# Tui.net
KiCad netlist of a schematic drawn in Altium Designer
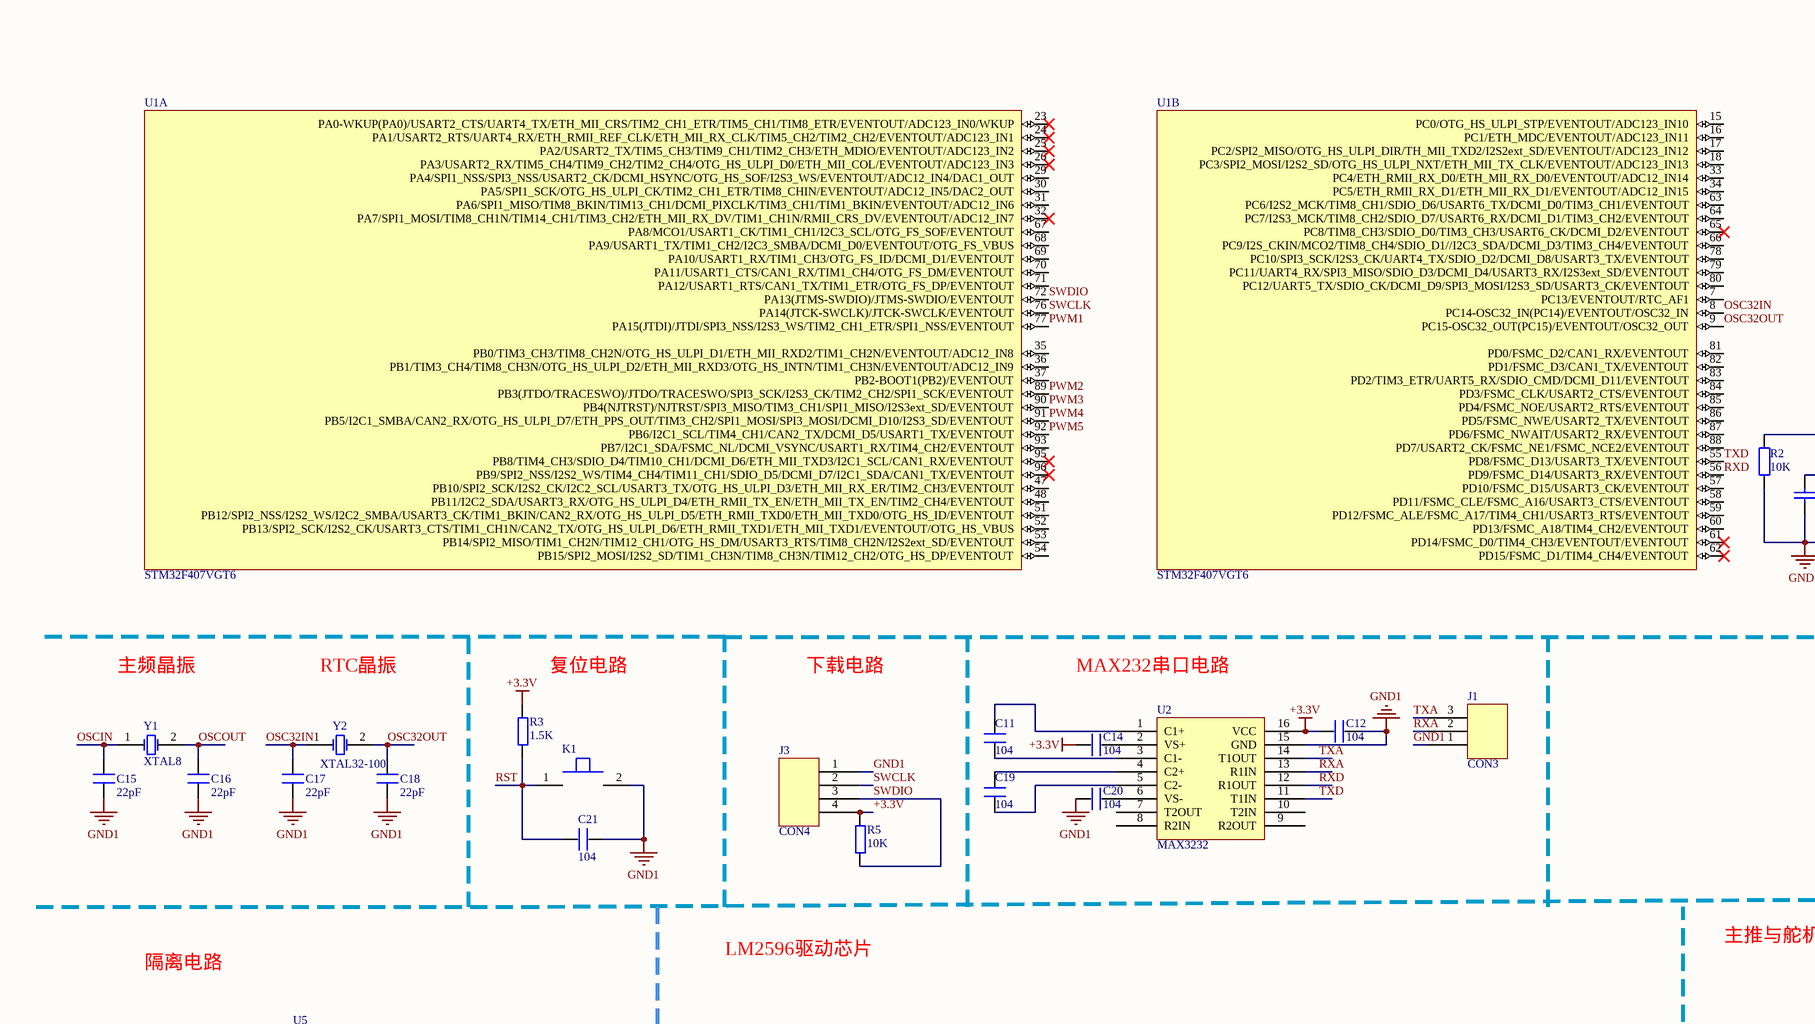
[diagram p0: Tui.SchDoc, top left]
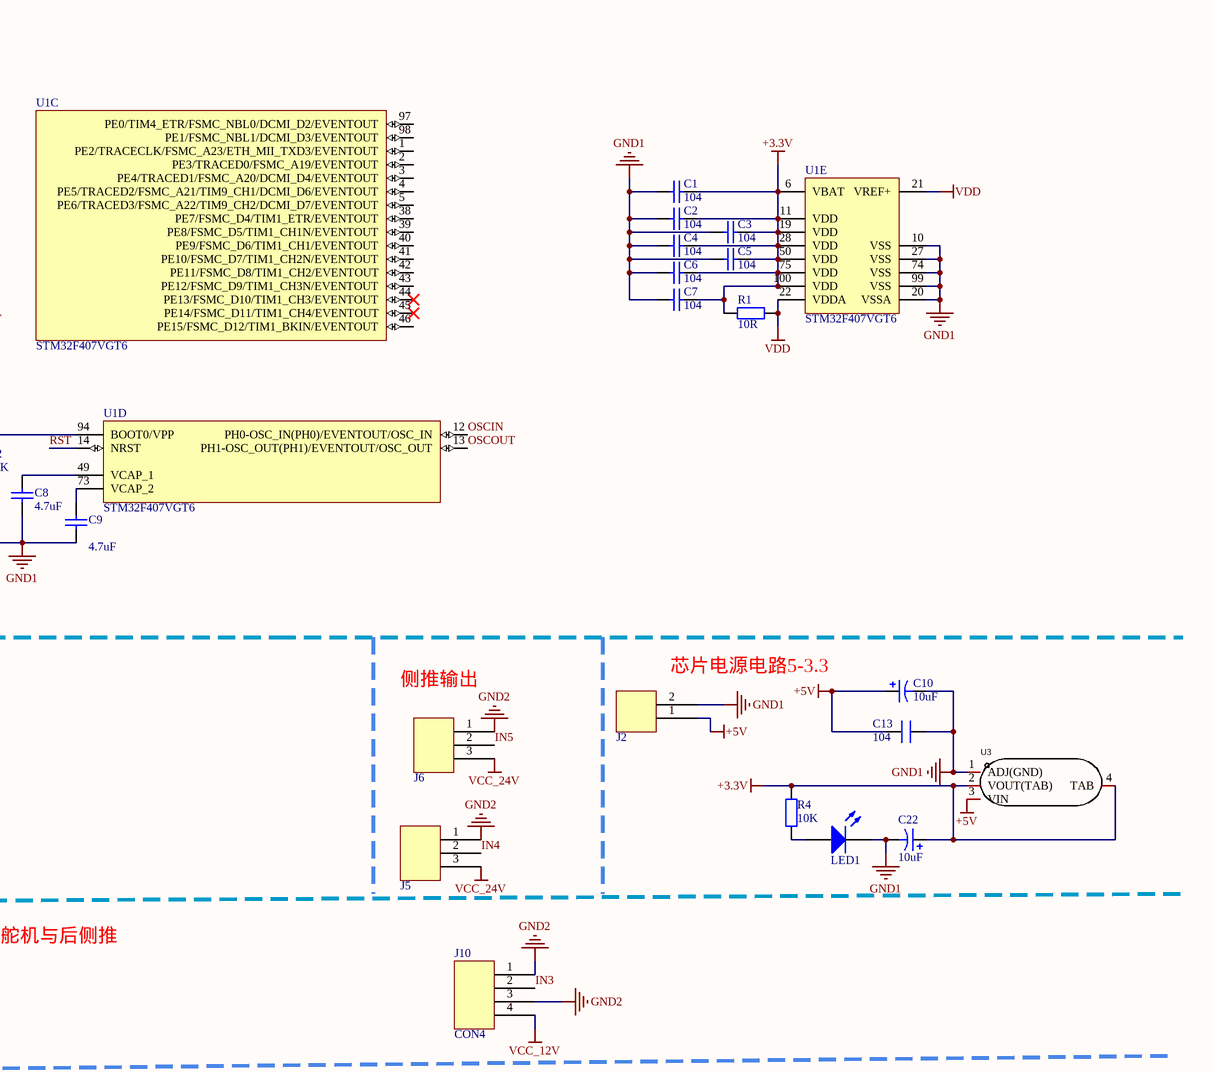
[diagram p1: Tui.SchDoc, top right]
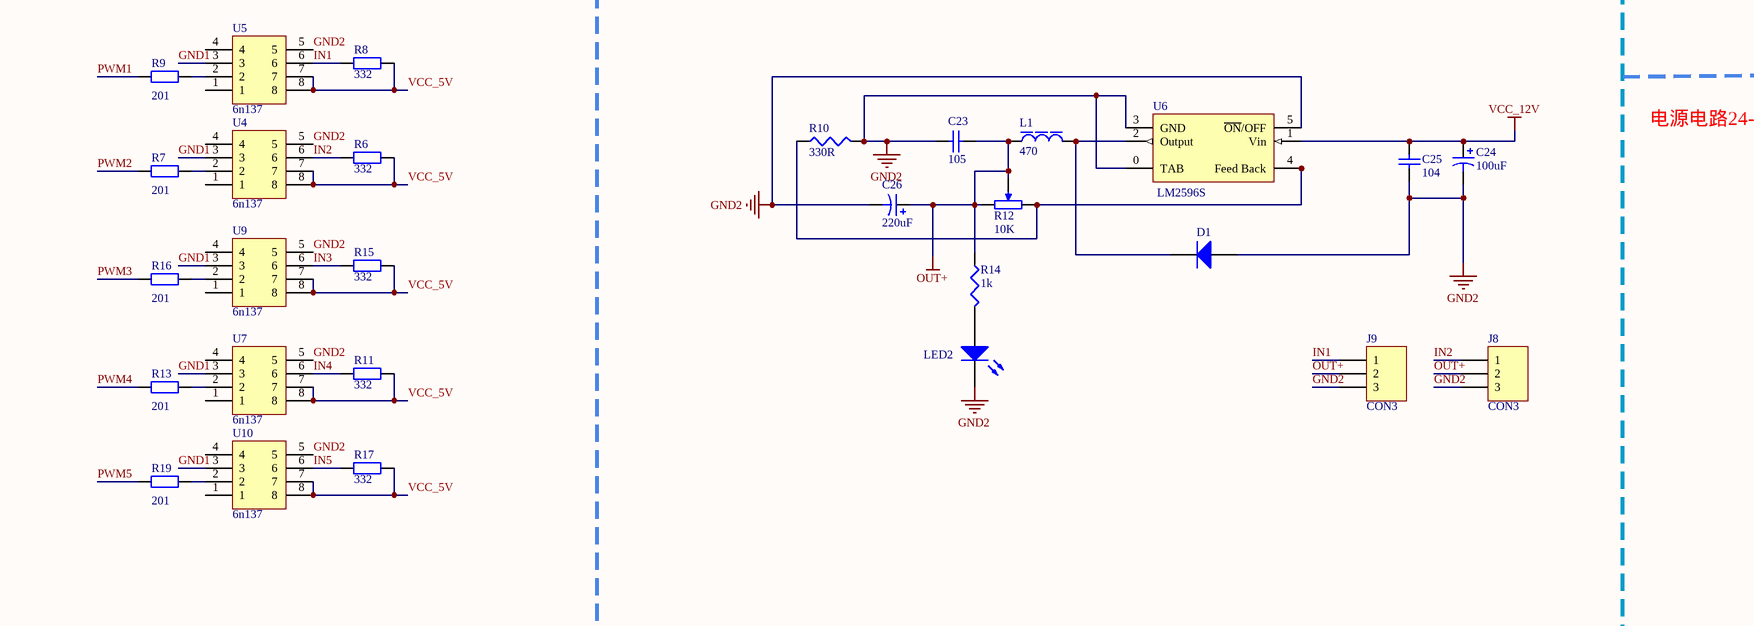
[diagram p2: Tui.SchDoc, bottom left]
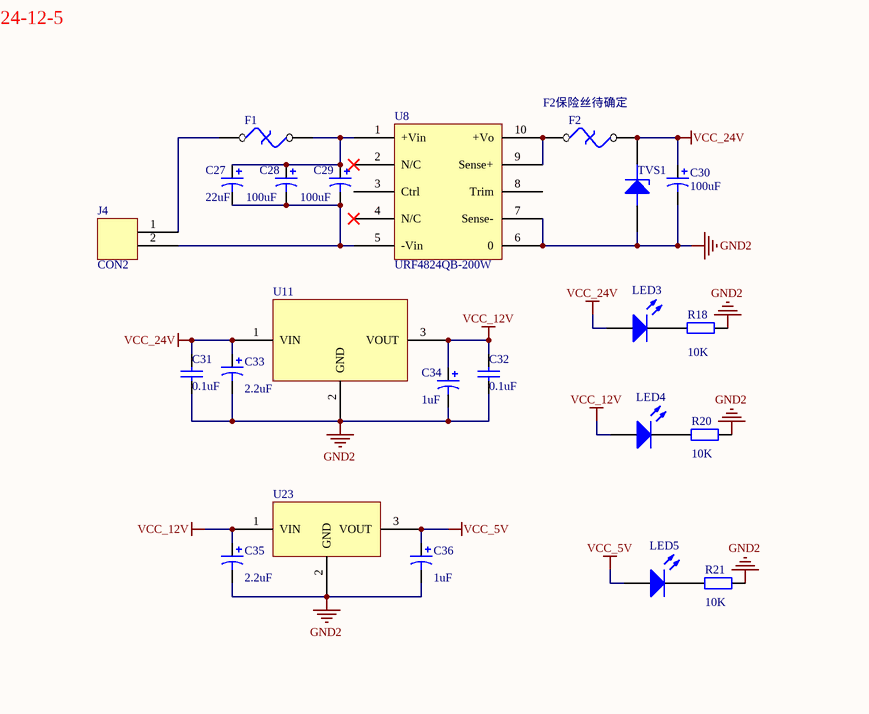
[diagram p3: Tui.SchDoc, bottom right]

(export (version "E")
  (design (tool "Eeschema 10.0.6"))
  (components
    (comp (ref "C1")
      (value "104")
      (footprint "0805")
      (description "Capacitor")
      (fields (field (name "PUBLISHER") "Altium Limited"))
      (libsource (lib "Miscellaneous Devices") (part "Cap"))
    )
    (comp (ref "C2")
      (value "104")
      (footprint "0805")
      (description "Capacitor")
      (fields (field (name "PUBLISHER") "Altium Limited"))
      (libsource (lib "Miscellaneous Devices") (part "Cap"))
    )
    (comp (ref "C3")
      (value "104")
      (footprint "0805")
      (description "Capacitor")
      (fields (field (name "PUBLISHER") "Altium Limited"))
      (libsource (lib "Miscellaneous Devices") (part "Cap"))
    )
    (comp (ref "C4")
      (value "104")
      (footprint "0805")
      (description "Capacitor")
      (fields (field (name "PUBLISHER") "Altium Limited"))
      (libsource (lib "Miscellaneous Devices") (part "Cap"))
    )
    (comp (ref "C5")
      (value "104")
      (footprint "0805")
      (description "Capacitor")
      (fields (field (name "PUBLISHER") "Altium Limited"))
      (libsource (lib "Miscellaneous Devices") (part "Cap"))
    )
    (comp (ref "C6")
      (value "104")
      (footprint "0805")
      (description "Capacitor")
      (fields (field (name "PUBLISHER") "Altium Limited"))
      (libsource (lib "Miscellaneous Devices") (part "Cap"))
    )
    (comp (ref "C7")
      (value "104")
      (footprint "0805")
      (description "Capacitor")
      (fields (field (name "PUBLISHER") "Altium Limited"))
      (libsource (lib "Miscellaneous Devices") (part "Cap"))
    )
    (comp (ref "C8")
      (value "4.7uF")
      (footprint "0805")
      (description "Capacitor")
      (fields (field (name "PUBLISHER") "Altium Limited"))
      (libsource (lib "Miscellaneous Devices") (part "Cap"))
    )
    (comp (ref "C9")
      (value "4.7uF")
      (footprint "0805")
      (description "Capacitor")
      (fields (field (name "PUBLISHER") "Altium Limited"))
      (libsource (lib "Miscellaneous Devices") (part "Cap"))
    )
    (comp (ref "C10")
      (value "10uF")
      (footprint "钽电容小")
      (description "Polarized Capacitor (Radial)")
      (fields (field (name "Comment") "Cap Pol1") (field (name "PUBLISHER") "Altium Limited"))
      (libsource (lib "Miscellaneous Devices") (part "Cap Pol1"))
    )
    (comp (ref "C11") (value "104") (footprint "0805") (libsource (lib "stm32") (part "CAP")))
    (comp (ref "C12") (value "104") (footprint "0805") (libsource (lib "stm32") (part "CAP")))
    (comp (ref "C13") (value "104") (footprint "0805") (libsource (lib "stm32") (part "CAP")))
    (comp (ref "C14") (value "104") (footprint "0805") (libsource (lib "stm32") (part "CAP")))
    (comp (ref "C15") (value "22pF") (footprint "0805") (libsource (lib "stm32") (part "CAP")))
    (comp (ref "C16") (value "22pF") (footprint "0805") (libsource (lib "stm32") (part "CAP")))
    (comp (ref "C17") (value "22pF") (footprint "0805") (libsource (lib "stm32") (part "CAP")))
    (comp (ref "C18") (value "22pF") (footprint "0805") (libsource (lib "stm32") (part "CAP")))
    (comp (ref "C19") (value "104") (footprint "0805") (libsource (lib "stm32") (part "CAP")))
    (comp (ref "C20") (value "104") (footprint "0805") (libsource (lib "stm32") (part "CAP")))
    (comp (ref "C21") (value "104") (footprint "0805") (libsource (lib "stm32") (part "CAP")))
    (comp (ref "C22")
      (value "10uF")
      (footprint "钽电容小")
      (description "Polarized Capacitor (Radial)")
      (fields (field (name "Comment") "Cap Pol1") (field (name "PUBLISHER") "Altium Limited"))
      (libsource (lib "Miscellaneous Devices") (part "Cap Pol1"))
    )
    (comp (ref "C23")
      (value "105")
      (footprint "0805")
      (description "Capacitor (Semiconductor SIM Model)")
      (libsource (lib "FPGA_A") (part "Cap Semi"))
    )
    (comp (ref "C24")
      (value "100uF")
      (footprint "CAP+")
      (description "Polarized Capacitor (Radial)")
      (fields (field (name "Comment") "107T") (field (name "PUBLISHER") "Altium Limited"))
      (libsource (lib "FPGA_A") (part "Cap Pol1"))
    )
    (comp (ref "C25")
      (value "104")
      (footprint "0805")
      (description "Capacitor (Semiconductor SIM Model)")
      (libsource (lib "FPGA_A") (part "Cap Semi_1"))
    )
    (comp (ref "C26")
      (value "220uF")
      (footprint "CAP+")
      (description "Polarized Capacitor (Radial)")
      (fields (field (name "Comment") "227V") (field (name "PUBLISHER") "Altium Limited"))
      (libsource (lib "FPGA_A") (part "Cap Pol1"))
    )
    (comp (ref "C27")
      (value "22uF")
      (footprint "钽电容大")
      (description "Polarized Capacitor (Radial)")
      (fields (field (name "Comment") "Cap Pol1") (field (name "PUBLISHER") "Altium Limited"))
      (libsource (lib "Miscellaneous Devices") (part "Cap Pol1"))
    )
    (comp (ref "C28")
      (value "100uF")
      (footprint "钽电容大")
      (description "Polarized Capacitor (Radial)")
      (fields (field (name "Comment") "Cap Pol1") (field (name "PUBLISHER") "Altium Limited"))
      (libsource (lib "Miscellaneous Devices") (part "Cap Pol1"))
    )
    (comp (ref "C29")
      (value "100uF")
      (footprint "钽电容大")
      (description "Polarized Capacitor (Radial)")
      (fields (field (name "Comment") "Cap Pol1") (field (name "PUBLISHER") "Altium Limited"))
      (libsource (lib "Miscellaneous Devices") (part "Cap Pol1"))
    )
    (comp (ref "C30")
      (value "100uF")
      (footprint "钽电容大")
      (description "Polarized Capacitor (Radial)")
      (fields (field (name "Comment") "Cap Pol1") (field (name "PUBLISHER") "Altium Limited"))
      (libsource (lib "Miscellaneous Devices") (part "Cap Pol1"))
    )
    (comp (ref "C31")
      (value "0.1uF")
      (footprint "0805")
      (description "Capacitor")
      (fields (field (name "PUBLISHER") "Altium Limited"))
      (libsource (lib "Miscellaneous Devices") (part "Cap"))
    )
    (comp (ref "C32")
      (value "0.1uF")
      (footprint "0805")
      (description "Capacitor")
      (fields (field (name "PUBLISHER") "Altium Limited"))
      (libsource (lib "Miscellaneous Devices") (part "Cap"))
    )
    (comp (ref "C33")
      (value "2.2uF")
      (footprint "钽电容小")
      (description "Polarized Capacitor (Radial)")
      (fields (field (name "Comment") "Cap Pol1") (field (name "PUBLISHER") "Altium Limited"))
      (libsource (lib "Miscellaneous Devices") (part "Cap Pol1"))
    )
    (comp (ref "C34")
      (value "1uF")
      (footprint "钽电容小")
      (description "Polarized Capacitor (Radial)")
      (fields (field (name "Comment") "Cap Pol1") (field (name "PUBLISHER") "Altium Limited"))
      (libsource (lib "Miscellaneous Devices") (part "Cap Pol1"))
    )
    (comp (ref "C35")
      (value "2.2uF")
      (footprint "钽电容小")
      (description "Polarized Capacitor (Radial)")
      (fields (field (name "Comment") "Cap Pol1") (field (name "PUBLISHER") "Altium Limited"))
      (libsource (lib "Miscellaneous Devices") (part "Cap Pol1"))
    )
    (comp (ref "C36")
      (value "1uF")
      (footprint "钽电容小")
      (description "Polarized Capacitor (Radial)")
      (fields (field (name "Comment") "Cap Pol1") (field (name "PUBLISHER") "Altium Limited"))
      (libsource (lib "Miscellaneous Devices") (part "Cap Pol1"))
    )
    (comp (ref "D1") (value "DIODE") (footprint "SS34") (libsource (lib "原理图库") (part "DIODE")))
    (comp (ref "F1")
      (value "THERMAL FUSE")
      (footprint "1206")
      (libsource (lib "Miscellaneous Devices") (part "THERMAL FUSE"))
    )
    (comp (ref "F2")
      (value "THERMAL FUSE")
      (footprint "1206")
      (libsource (lib "Miscellaneous Devices") (part "THERMAL FUSE"))
    )
    (comp (ref "J1") (value "CON3") (footprint "CON3BB") (libsource (lib "") (part "CON3_1")))
    (comp (ref "J2")
      (value "CON2")
      (footprint "CONN-TH_2P-P3.81_DB2EVC-3.81-2P-BK")
      (libsource (lib "stm32") (part "CON2"))
    )
    (comp (ref "J3") (value "CON4") (footprint "CON4") (libsource (lib "stm32") (part "CON4")))
    (comp (ref "J4")
      (value "CON2")
      (footprint "CONN-TH_2P-P3.81_DB2EVC-3.81-2P-BK")
      (libsource (lib "") (part "CON2_1"))
    )
    (comp (ref "J5")
      (value "CON3")
      (footprint "CONN-TH_3P-P3.81_DB2EVC-3.81-3P")
      (libsource (lib "stm32") (part "CON3"))
    )
    (comp (ref "J6")
      (value "CON3")
      (footprint "CONN-TH_3P-P3.81_DB2EVC-3.81-3P")
      (libsource (lib "stm32") (part "CON3"))
    )
    (comp (ref "J8")
      (value "CON3")
      (footprint "CONN-TH_3P-P3.81_DB2EVC-3.81-3P")
      (description "Header, 3-Pin")
      (fields (field (name "PUBLISHER") "Altium Limited"))
      (libsource (lib "Miscellaneous Connectors") (part "Header 3"))
    )
    (comp (ref "J9")
      (value "CON3")
      (footprint "CONN-TH_3P-P3.81_DB2EVC-3.81-3P")
      (description "Header, 3-Pin")
      (fields (field (name "PUBLISHER") "Altium Limited"))
      (libsource (lib "Miscellaneous Connectors") (part "Header 3"))
    )
    (comp (ref "J10")
      (value "CON4")
      (footprint "CONN-TH_4P-P3.81_DB2EVC-3.81-4P")
      (libsource (lib "stm32") (part "CON4"))
    )
    (comp (ref "K1") (value "KEY4") (footprint "按钮") (libsource (lib "stm32") (part "KEY4")))
    (comp (ref "L1") (value "470") (footprint "470") (libsource (lib "原理图库") (part "470")))
    (comp (ref "LED1")
      (value "LED")
      (footprint "0805")
      (fields (field (name "PUBLISHER") "Altium Limited"))
      (libsource (lib "stm32") (part "LED"))
    )
    (comp (ref "LED2")
      (value "~")
      (footprint "0805")
      (description "Typical RED, GREEN, YELLOW, AMBER GaAs LED")
      (libsource (lib "Miscellaneous Devices") (part "LED2"))
    )
    (comp (ref "LED3")
      (value "LED")
      (footprint "0805")
      (fields (field (name "PUBLISHER") "Altium Limited"))
      (libsource (lib "stm32") (part "LED"))
    )
    (comp (ref "LED4")
      (value "LED")
      (footprint "0805")
      (fields (field (name "PUBLISHER") "Altium Limited"))
      (libsource (lib "stm32") (part "LED"))
    )
    (comp (ref "LED5")
      (value "LED")
      (footprint "0805")
      (fields (field (name "PUBLISHER") "Altium Limited"))
      (libsource (lib "stm32") (part "LED"))
    )
    (comp (ref "R1")
      (value "10R")
      (footprint "0805")
      (description "Resistor")
      (fields (field (name "PUBLISHER") "Altium Limited"))
      (libsource (lib "") (part "Res2_1"))
    )
    (comp (ref "R2")
      (value "10K")
      (footprint "0805")
      (description "Resistor")
      (fields (field (name "PUBLISHER") "Altium Limited"))
      (libsource (lib "") (part "Res2_3"))
    )
    (comp (ref "R3") (value "1.5K") (footprint "0805") (libsource (lib "stm32") (part "RES")))
    (comp (ref "R4")
      (value "10K")
      (footprint "0805")
      (description "Resistor")
      (fields (field (name "PUBLISHER") "Altium Limited"))
      (libsource (lib "") (part "Res2_2"))
    )
    (comp (ref "R5") (value "10K") (footprint "0805") (libsource (lib "stm32") (part "RES")))
    (comp (ref "R6")
      (value "332")
      (footprint "0805")
      (description "Resistor")
      (fields (field (name "PUBLISHER") "Altium Limited"))
      (libsource (lib "") (part "Res2_1"))
    )
    (comp (ref "R7")
      (value "201")
      (footprint "0805")
      (description "Resistor")
      (fields (field (name "PUBLISHER") "Altium Limited"))
      (libsource (lib "Miscellaneous Devices") (part "Res2"))
    )
    (comp (ref "R8")
      (value "332")
      (footprint "0805")
      (description "Resistor")
      (fields (field (name "PUBLISHER") "Altium Limited"))
      (libsource (lib "") (part "Res2_1"))
    )
    (comp (ref "R9")
      (value "201")
      (footprint "0805")
      (description "Resistor")
      (fields (field (name "PUBLISHER") "Altium Limited"))
      (libsource (lib "Miscellaneous Devices") (part "Res2"))
    )
    (comp (ref "R10")
      (value "330R")
      (footprint "0805")
      (description "Resistor")
      (libsource (lib "FPGA_A") (part "Res3"))
    )
    (comp (ref "R11")
      (value "332")
      (footprint "0805")
      (description "Resistor")
      (fields (field (name "PUBLISHER") "Altium Limited"))
      (libsource (lib "") (part "Res2_1"))
    )
    (comp (ref "R12") (value "10K") (footprint "RESPACK") (libsource (lib "原理图库") (part "RESPACK")))
    (comp (ref "R13")
      (value "201")
      (footprint "0805")
      (description "Resistor")
      (fields (field (name "PUBLISHER") "Altium Limited"))
      (libsource (lib "Miscellaneous Devices") (part "Res2"))
    )
    (comp (ref "R14") (value "1k") (footprint "0805") (libsource (lib "FPGA_A") (part "RES")))
    (comp (ref "R15")
      (value "332")
      (footprint "0805")
      (description "Resistor")
      (fields (field (name "PUBLISHER") "Altium Limited"))
      (libsource (lib "") (part "Res2_1"))
    )
    (comp (ref "R16")
      (value "201")
      (footprint "0805")
      (description "Resistor")
      (fields (field (name "PUBLISHER") "Altium Limited"))
      (libsource (lib "Miscellaneous Devices") (part "Res2"))
    )
    (comp (ref "R17")
      (value "332")
      (footprint "0805")
      (description "Resistor")
      (fields (field (name "PUBLISHER") "Altium Limited"))
      (libsource (lib "") (part "Res2_1"))
    )
    (comp (ref "R18")
      (value "10K")
      (footprint "0805")
      (description "Resistor")
      (fields (field (name "Comment") "Res2") (field (name "PUBLISHER") "Altium Limited"))
      (libsource (lib "Miscellaneous Devices") (part "Res2"))
    )
    (comp (ref "R19")
      (value "201")
      (footprint "0805")
      (description "Resistor")
      (fields (field (name "PUBLISHER") "Altium Limited"))
      (libsource (lib "Miscellaneous Devices") (part "Res2"))
    )
    (comp (ref "R20")
      (value "10K")
      (footprint "0805")
      (description "Resistor")
      (fields (field (name "PUBLISHER") "Altium Limited"))
      (libsource (lib "Miscellaneous Devices") (part "Res2"))
    )
    (comp (ref "R21")
      (value "10K")
      (footprint "0805")
      (description "Resistor")
      (fields (field (name "PUBLISHER") "Altium Limited"))
      (libsource (lib "Miscellaneous Devices") (part "Res2"))
    )
    (comp (ref "TVS1")
      (value "TVS")
      (footprint "tvs")
      (description "Zener Diode")
      (libsource (lib "二极管") (part "稳压二极管"))
    )
    (comp (ref "U1")
      (value "STM32F407VGT6")
      (footprint "STM32F407VGT6")
      (libsource (lib "STM32 F4") (part "STM32F407VGT6"))
    )
    (comp (ref "U2") (value "MAX3232") (footprint "max3232") (libsource (lib "Schlib1") (part "MAX3232")))
    (comp (ref "U3")
      (value "AMS1117-3.3_C347222")
      (footprint "AMS1117")
      (fields (field (name "MANUFACTURER") "UMW(广东友台半导体)") (field (name "MANUFACTURER PART") "AMS1117-3.3"))
      (libsource (lib "altium-import") (part "root_0_AMS1117-3.3_C347222_"))
    )
    (comp (ref "U4") (value "6n137") (footprint "6n137") (libsource (lib "6n137") (part "6n137")))
    (comp (ref "U5") (value "6n137") (footprint "6n137") (libsource (lib "6n137") (part "6n137")))
    (comp (ref "U6") (value "LM2596S") (footprint "LM2596S") (libsource (lib "原理图库") (part "LM2596S")))
    (comp (ref "U7") (value "6n137") (footprint "6n137") (libsource (lib "6n137") (part "6n137")))
    (comp (ref "U8")
      (value "URF4824QB-200W")
      (footprint "URF4824QB-200W（24稳压）")
      (libsource (lib "Schlib1") (part "URF4824QB-200W"))
    )
    (comp (ref "U9") (value "6n137") (footprint "6n137") (libsource (lib "6n137") (part "6n137")))
    (comp (ref "U10") (value "6n137") (footprint "6n137") (libsource (lib "6n137") (part "6n137")))
    (comp (ref "U11") (value "7812") (footprint "7812") (libsource (lib "Schlib1") (part "L7912CV")))
    (comp (ref "U23") (value "7805") (footprint "7805") (libsource (lib "Schlib1") (part "7805")))
    (comp (ref "Y1")
      (value "XTAL8")
      (footprint "XTAL8（晶振）")
      (fields (field (name "PUBLISHER") "Altium Limited"))
      (libsource (lib "stm32") (part "XTAL8"))
    )
    (comp (ref "Y2")
      (value "XTAL32-100")
      (footprint "XTAL32-100（晶振）")
      (fields (field (name "PUBLISHER") "Altium Limited"))
      (libsource (lib "stm32") (part "XTAL32-100"))
    )
  )
  (nets
    (net (code "1") (name "+3.3V") (class "Default")
      (node (ref "C1") (pin "1") (pinfunction "1_1") (pintype "passive"))
      (node (ref "C12") (pin "1") (pintype "passive"))
      (node (ref "C14") (pin "2") (pintype "passive"))
      (node (ref "C2") (pin "1") (pinfunction "1_1") (pintype "passive"))
      (node (ref "C22") (pin "1") (pinfunction "1_1") (pintype "passive"))
      (node (ref "C3") (pin "1") (pinfunction "1_1") (pintype "passive"))
      (node (ref "C4") (pin "1") (pinfunction "1_1") (pintype "passive"))
      (node (ref "C5") (pin "1") (pinfunction "1_1") (pintype "passive"))
      (node (ref "C6") (pin "1") (pinfunction "1_1") (pintype "passive"))
      (node (ref "C7") (pin "1") (pinfunction "1_1") (pintype "passive"))
      (node (ref "J3") (pin "4") (pinfunction "4_4") (pintype "passive"))
      (node (ref "R1") (pin "2") (pinfunction "2_2") (pintype "passive"))
      (node (ref "R3") (pin "2") (pintype "passive"))
      (node (ref "R4") (pin "2") (pinfunction "2_2") (pintype "passive"))
      (node (ref "R5") (pin "2") (pintype "passive"))
      (node (ref "U1") (pin "100") (pinfunction "VDD_100") (pintype "power_in"))
      (node (ref "U1") (pin "11") (pinfunction "VDD_11") (pintype "power_in"))
      (node (ref "U1") (pin "19") (pinfunction "VDD_19") (pintype "power_in"))
      (node (ref "U1") (pin "28") (pinfunction "VDD_28") (pintype "power_in"))
      (node (ref "U1") (pin "50") (pinfunction "VDD_50") (pintype "power_in"))
      (node (ref "U1") (pin "6") (pinfunction "VBAT_6") (pintype "power_in"))
      (node (ref "U1") (pin "75") (pinfunction "VDD_75") (pintype "power_in"))
      (node (ref "U2") (pin "16") (pinfunction "VCC_16") (pintype "power_in"))
      (node (ref "U3") (pin "2") (pinfunction "VOUT(TAB)_2") (pintype "passive"))
      (node (ref "U3") (pin "4") (pinfunction "TAB_4") (pintype "passive"))
    )
    (net (code "2") (name "+5V") (class "Default")
      (node (ref "C10") (pin "1") (pinfunction "1_1") (pintype "passive"))
      (node (ref "C13") (pin "2") (pintype "passive"))
      (node (ref "J2") (pin "1") (pinfunction "1_1") (pintype "passive"))
      (node (ref "U3") (pin "3") (pinfunction "VIN_3") (pintype "passive"))
    )
    (net (code "3") (name "/IN1") (class "Default")
      (node (ref "J9") (pin "1") (pinfunction "1_1") (pintype "passive"))
      (node (ref "R8") (pin "2") (pinfunction "2_2") (pintype "passive"))
      (node (ref "U5") (pin "6") (pinfunction "6_6") (pintype "passive"))
    )
    (net (code "4") (name "/IN2") (class "Default")
      (node (ref "J8") (pin "1") (pinfunction "1_1") (pintype "passive"))
      (node (ref "R6") (pin "2") (pinfunction "2_2") (pintype "passive"))
      (node (ref "U4") (pin "6") (pinfunction "6_6") (pintype "passive"))
    )
    (net (code "5") (name "/IN3") (class "Default")
      (node (ref "J10") (pin "2") (pinfunction "2_2") (pintype "passive"))
      (node (ref "R15") (pin "2") (pinfunction "2_2") (pintype "passive"))
      (node (ref "U9") (pin "6") (pinfunction "6_6") (pintype "passive"))
    )
    (net (code "6") (name "/IN4") (class "Default")
      (node (ref "J5") (pin "2") (pinfunction "2_2") (pintype "passive"))
      (node (ref "R11") (pin "2") (pinfunction "2_2") (pintype "passive"))
      (node (ref "U7") (pin "6") (pinfunction "6_6") (pintype "passive"))
    )
    (net (code "7") (name "/IN5") (class "Default")
      (node (ref "J6") (pin "2") (pinfunction "2_2") (pintype "passive"))
      (node (ref "R17") (pin "2") (pinfunction "2_2") (pintype "passive"))
      (node (ref "U10") (pin "6") (pinfunction "6_6") (pintype "passive"))
    )
    (net (code "8") (name "/OSC32IN") (class "Default")
      (node (ref "C17") (pin "2") (pintype "passive"))
      (node (ref "U1") (pin "8") (pinfunction "PC14-OSC32_IN(PC14)/EVENTOUT/OSC32_IN_8") (pintype "bidirectional"))
      (node (ref "Y2") (pin "1") (pinfunction "OSC1_1") (pintype "passive"))
    )
    (net (code "9") (name "/OSC32OUT") (class "Default")
      (node (ref "C18") (pin "2") (pintype "passive"))
      (node (ref "U1") (pin "9") (pinfunction "PC15-OSC32_OUT(PC15)/EVENTOUT/OSC32_OUT_9") (pintype "bidirectional"))
      (node (ref "Y2") (pin "2") (pinfunction "OSC2_2") (pintype "passive"))
    )
    (net (code "10") (name "/OSCIN") (class "Default")
      (node (ref "C15") (pin "2") (pintype "passive"))
      (node (ref "U1") (pin "12") (pinfunction "PH0-OSC_IN(PH0)/EVENTOUT/OSC_IN_12") (pintype "bidirectional"))
      (node (ref "Y1") (pin "1") (pinfunction "OSC1_1") (pintype "passive"))
    )
    (net (code "11") (name "/OSCOUT") (class "Default")
      (node (ref "C16") (pin "2") (pintype "passive"))
      (node (ref "U1") (pin "13") (pinfunction "PH1-OSC_OUT(PH1)/EVENTOUT/OSC_OUT_13") (pintype "bidirectional"))
      (node (ref "Y1") (pin "2") (pinfunction "OSC2_2") (pintype "passive"))
    )
    (net (code "12") (name "/PWM1") (class "Default")
      (node (ref "R9") (pin "1") (pinfunction "1_1") (pintype "passive"))
      (node (ref "U1") (pin "77") (pinfunction "PA15(JTDI)/JTDI/SPI3_NSS/I2S3_WS/TIM2_CH1_ETR/SPI1_NSS/EVENTOUT_77") (pintype "bidirectional"))
    )
    (net (code "13") (name "/PWM2") (class "Default")
      (node (ref "R7") (pin "1") (pinfunction "1_1") (pintype "passive"))
      (node (ref "U1") (pin "89") (pinfunction "PB3(JTDO/TRACESWO)/JTDO/TRACESWO/SPI3_SCK/I2S3_CK/TIM2_CH2/SPI1_SCK/EVENTOUT_89") (pintype "bidirectional"))
    )
    (net (code "14") (name "/PWM3") (class "Default")
      (node (ref "R16") (pin "1") (pinfunction "1_1") (pintype "passive"))
      (node (ref "U1") (pin "90") (pinfunction "PB4(NJTRST)/NJTRST/SPI3_MISO/TIM3_CH1/SPI1_MISO/I2S3ext_SD/EVENTOUT_90") (pintype "bidirectional"))
    )
    (net (code "15") (name "/PWM4") (class "Default")
      (node (ref "R13") (pin "1") (pinfunction "1_1") (pintype "passive"))
      (node (ref "U1") (pin "91") (pinfunction "PB5/I2C1_SMBA/CAN2_RX/OTG_HS_ULPI_D7/ETH_PPS_OUT/TIM3_CH2/SPI1_MOSI/SPI3_MOSI/DCMI_D10/I2S3_SD/EVENTOUT_91") (pintype "bidirectional"))
    )
    (net (code "16") (name "/PWM5") (class "Default")
      (node (ref "R19") (pin "1") (pinfunction "1_1") (pintype "passive"))
      (node (ref "U1") (pin "92") (pinfunction "PB6/I2C1_SCL/TIM4_CH1/CAN2_TX/DCMI_D5/USART1_TX/EVENTOUT_92") (pintype "bidirectional"))
    )
    (net (code "17") (name "/RST") (class "Default")
      (node (ref "C21") (pin "1") (pintype "passive"))
      (node (ref "K1") (pin "1") (pinfunction "1_1") (pintype "passive"))
      (node (ref "R3") (pin "1") (pintype "passive"))
      (node (ref "U1") (pin "14") (pinfunction "NRST_14") (pintype "bidirectional"))
    )
    (net (code "18") (name "/RXA") (class "Default")
      (node (ref "J1") (pin "2") (pinfunction "2_2") (pintype "passive"))
      (node (ref "U2") (pin "13") (pinfunction "R1IN_13") (pintype "power_in"))
    )
    (net (code "19") (name "/RXD") (class "Default")
      (node (ref "U1") (pin "56") (pinfunction "PD9/FSMC_D14/USART3_RX/EVENTOUT_56") (pintype "bidirectional"))
      (node (ref "U2") (pin "12") (pinfunction "R1OUT_12") (pintype "power_in"))
    )
    (net (code "20") (name "/SWCLK") (class "Default")
      (node (ref "J3") (pin "2") (pinfunction "2_2") (pintype "passive"))
      (node (ref "U1") (pin "76") (pinfunction "PA14(JTCK-SWCLK)/JTCK-SWCLK/EVENTOUT_76") (pintype "bidirectional"))
    )
    (net (code "21") (name "/SWDIO") (class "Default")
      (node (ref "J3") (pin "3") (pinfunction "3_3") (pintype "passive"))
      (node (ref "R5") (pin "1") (pintype "passive"))
      (node (ref "U1") (pin "72") (pinfunction "PA13(JTMS-SWDIO)/JTMS-SWDIO/EVENTOUT_72") (pintype "bidirectional"))
    )
    (net (code "22") (name "/TXA") (class "Default")
      (node (ref "J1") (pin "3") (pinfunction "3_3") (pintype "passive"))
      (node (ref "U2") (pin "14") (pinfunction "T1OUT_14") (pintype "power_in"))
    )
    (net (code "23") (name "/TXD") (class "Default")
      (node (ref "U1") (pin "55") (pinfunction "PD8/FSMC_D13/USART3_TX/EVENTOUT_55") (pintype "bidirectional"))
      (node (ref "U2") (pin "11") (pinfunction "T1IN_11") (pintype "power_in"))
    )
    (net (code "24") (name "GND1") (class "Default")
      (node (ref "C1") (pin "2") (pinfunction "2_2") (pintype "passive"))
      (node (ref "C10") (pin "2") (pinfunction "2_2") (pintype "passive"))
      (node (ref "C12") (pin "2") (pintype "passive"))
      (node (ref "C13") (pin "1") (pintype "passive"))
      (node (ref "C15") (pin "1") (pintype "passive"))
      (node (ref "C16") (pin "1") (pintype "passive"))
      (node (ref "C17") (pin "1") (pintype "passive"))
      (node (ref "C18") (pin "1") (pintype "passive"))
      (node (ref "C2") (pin "2") (pinfunction "2_2") (pintype "passive"))
      (node (ref "C20") (pin "1") (pintype "passive"))
      (node (ref "C21") (pin "2") (pintype "passive"))
      (node (ref "C22") (pin "2") (pinfunction "2_2") (pintype "passive"))
      (node (ref "C3") (pin "2") (pinfunction "2_2") (pintype "passive"))
      (node (ref "C4") (pin "2") (pinfunction "2_2") (pintype "passive"))
      (node (ref "C5") (pin "2") (pinfunction "2_2") (pintype "passive"))
      (node (ref "C6") (pin "2") (pinfunction "2_2") (pintype "passive"))
      (node (ref "C7") (pin "2") (pinfunction "2_2") (pintype "passive"))
      (node (ref "C8") (pin "1") (pinfunction "1_1") (pintype "passive"))
      (node (ref "C9") (pin "1") (pinfunction "1_1") (pintype "passive"))
      (node (ref "J1") (pin "1") (pinfunction "1_1") (pintype "passive"))
      (node (ref "J2") (pin "2") (pinfunction "2_2") (pintype "passive"))
      (node (ref "J3") (pin "1") (pinfunction "1_1") (pintype "passive"))
      (node (ref "K1") (pin "2") (pinfunction "2_2") (pintype "passive"))
      (node (ref "LED1") (pin "2") (pinfunction "K_2") (pintype "passive"))
      (node (ref "R2") (pin "2") (pinfunction "2_2") (pintype "passive"))
      (node (ref "U1") (pin "10") (pinfunction "VSS_10") (pintype "power_in"))
      (node (ref "U1") (pin "20") (pinfunction "VSSA_20") (pintype "power_in"))
      (node (ref "U1") (pin "27") (pinfunction "VSS_27") (pintype "power_in"))
      (node (ref "U1") (pin "74") (pinfunction "VSS_74") (pintype "power_in"))
      (node (ref "U1") (pin "99") (pinfunction "VSS_99") (pintype "power_in"))
      (node (ref "U10") (pin "3") (pinfunction "3_3") (pintype "passive"))
      (node (ref "U2") (pin "15") (pinfunction "GND_15") (pintype "power_in"))
      (node (ref "U3") (pin "1") (pinfunction "ADJ(GND)_1") (pintype "passive"))
      (node (ref "U4") (pin "3") (pinfunction "3_3") (pintype "passive"))
      (node (ref "U5") (pin "3") (pinfunction "3_3") (pintype "passive"))
      (node (ref "U7") (pin "3") (pinfunction "3_3") (pintype "passive"))
      (node (ref "U9") (pin "3") (pinfunction "3_3") (pintype "passive"))
    )
    (net (code "25") (name "GND2") (class "Default")
      (node (ref "C23") (pin "1") (pinfunction "1_1") (pintype "passive"))
      (node (ref "C24") (pin "2") (pinfunction "2_2") (pintype "passive"))
      (node (ref "C25") (pin "1") (pinfunction "1_1") (pintype "passive"))
      (node (ref "C26") (pin "2") (pinfunction "2_2") (pintype "passive"))
      (node (ref "C30") (pin "2") (pinfunction "2_2") (pintype "passive"))
      (node (ref "C31") (pin "1") (pinfunction "1_1") (pintype "passive"))
      (node (ref "C32") (pin "1") (pinfunction "1_1") (pintype "passive"))
      (node (ref "C33") (pin "2") (pinfunction "2_2") (pintype "passive"))
      (node (ref "C34") (pin "2") (pinfunction "2_2") (pintype "passive"))
      (node (ref "C35") (pin "2") (pinfunction "2_2") (pintype "passive"))
      (node (ref "C36") (pin "2") (pinfunction "2_2") (pintype "passive"))
      (node (ref "D1") (pin "1") (pinfunction "A_1") (pintype "passive"))
      (node (ref "J10") (pin "1") (pinfunction "1_1") (pintype "passive"))
      (node (ref "J10") (pin "3") (pinfunction "3_3") (pintype "passive"))
      (node (ref "J5") (pin "1") (pinfunction "1_1") (pintype "passive"))
      (node (ref "J6") (pin "1") (pinfunction "1_1") (pintype "passive"))
      (node (ref "J8") (pin "3") (pinfunction "3_3") (pintype "passive"))
      (node (ref "J9") (pin "3") (pinfunction "3_3") (pintype "passive"))
      (node (ref "LED2") (pin "2") (pinfunction "K_2") (pintype "passive"))
      (node (ref "R10") (pin "2") (pinfunction "2_2") (pintype "passive"))
      (node (ref "R18") (pin "2") (pinfunction "2_2") (pintype "passive"))
      (node (ref "R20") (pin "2") (pinfunction "2_2") (pintype "passive"))
      (node (ref "R21") (pin "2") (pinfunction "2_2") (pintype "passive"))
      (node (ref "TVS1") (pin "1") (pinfunction "A_1") (pintype "passive"))
      (node (ref "U10") (pin "5") (pinfunction "5_5") (pintype "passive"))
      (node (ref "U11") (pin "2") (pinfunction "GND_2") (pintype "passive"))
      (node (ref "U23") (pin "2") (pinfunction "GND_2") (pintype "passive"))
      (node (ref "U4") (pin "5") (pinfunction "5_5") (pintype "passive"))
      (node (ref "U5") (pin "5") (pinfunction "5_5") (pintype "passive"))
      (node (ref "U6") (pin "0") (pinfunction "TAB_0") (pintype "power_in"))
      (node (ref "U6") (pin "3") (pinfunction "GND_3") (pintype "power_in"))
      (node (ref "U6") (pin "5") (pinfunction "~{ON}/OFF_5") (pintype "power_in"))
      (node (ref "U7") (pin "5") (pinfunction "5_5") (pintype "passive"))
      (node (ref "U8") (pin "6") (pinfunction "0_6") (pintype "passive"))
      (node (ref "U8") (pin "7") (pinfunction "Sense-_7") (pintype "passive"))
      (node (ref "U9") (pin "5") (pinfunction "5_5") (pintype "passive"))
    )
    (net (code "26") (name "Net-(D1-K)") (class "Default")
      (node (ref "D1") (pin "2") (pinfunction "K_2") (pintype "passive"))
      (node (ref "L1") (pin "2") (pinfunction "2_2") (pintype "passive"))
      (node (ref "U6") (pin "2") (pinfunction "Output_2") (pintype "output"))
    )
    (net (code "27") (name "Net-(F1-Pad1)") (class "Default")
      (node (ref "F1") (pin "1") (pinfunction "1_1") (pintype "passive"))
      (node (ref "J4") (pin "1") (pinfunction "1_1") (pintype "passive"))
    )
    (net (code "28") (name "Net-(LED1-A)") (class "Default")
      (node (ref "LED1") (pin "1") (pinfunction "A_1") (pintype "passive"))
      (node (ref "R4") (pin "1") (pinfunction "1_1") (pintype "passive"))
    )
    (net (code "29") (name "Net-(LED2-A)") (class "Default")
      (node (ref "LED2") (pin "1") (pinfunction "A_1") (pintype "passive"))
      (node (ref "R14") (pin "2") (pinfunction "2_2") (pintype "passive"))
    )
    (net (code "30") (name "Net-(LED3-K)") (class "Default")
      (node (ref "LED3") (pin "2") (pinfunction "K_2") (pintype "passive"))
      (node (ref "R18") (pin "1") (pinfunction "1_1") (pintype "passive"))
    )
    (net (code "31") (name "Net-(LED4-K)") (class "Default")
      (node (ref "LED4") (pin "2") (pinfunction "K_2") (pintype "passive"))
      (node (ref "R20") (pin "1") (pinfunction "1_1") (pintype "passive"))
    )
    (net (code "32") (name "Net-(LED5-K)") (class "Default")
      (node (ref "LED5") (pin "2") (pinfunction "K_2") (pintype "passive"))
      (node (ref "R21") (pin "1") (pinfunction "1_1") (pintype "passive"))
    )
    (net (code "33") (name "Net-(R7-Pad2)") (class "Default")
      (node (ref "R7") (pin "2") (pinfunction "2_2") (pintype "passive"))
      (node (ref "U4") (pin "2") (pinfunction "2_2") (pintype "passive"))
    )
    (net (code "34") (name "Net-(R9-Pad2)") (class "Default")
      (node (ref "R9") (pin "2") (pinfunction "2_2") (pintype "passive"))
      (node (ref "U5") (pin "2") (pinfunction "2_2") (pintype "passive"))
    )
    (net (code "35") (name "Net-(R12-TOP)") (class "Default")
      (node (ref "R10") (pin "1") (pinfunction "1_1") (pintype "passive"))
      (node (ref "R12") (pin "1") (pinfunction "TOP_1") (pintype "passive"))
      (node (ref "U6") (pin "4") (pinfunction "Feed_Back_4") (pintype "power_in"))
    )
    (net (code "36") (name "Net-(R13-Pad2)") (class "Default")
      (node (ref "R13") (pin "2") (pinfunction "2_2") (pintype "passive"))
      (node (ref "U7") (pin "2") (pinfunction "2_2") (pintype "passive"))
    )
    (net (code "37") (name "Net-(R16-Pad2)") (class "Default")
      (node (ref "R16") (pin "2") (pinfunction "2_2") (pintype "passive"))
      (node (ref "U9") (pin "2") (pinfunction "2_2") (pintype "passive"))
    )
    (net (code "38") (name "Net-(R19-Pad2)") (class "Default")
      (node (ref "R19") (pin "2") (pinfunction "2_2") (pintype "passive"))
      (node (ref "U10") (pin "2") (pinfunction "2_2") (pintype "passive"))
    )
    (net (code "39") (name "Net-(U1D-BOOT0{slash}VPP)") (class "Default")
      (node (ref "R2") (pin "1") (pinfunction "1_1") (pintype "passive"))
      (node (ref "U1") (pin "94") (pinfunction "BOOT0/VPP_94") (pintype "input"))
    )
    (net (code "40") (name "Net-(U1D-VCAP_1)") (class "Default")
      (node (ref "C8") (pin "2") (pinfunction "2_2") (pintype "passive"))
      (node (ref "U1") (pin "49") (pinfunction "VCAP_1_49") (pintype "power_in"))
    )
    (net (code "41") (name "Net-(U1D-VCAP_2)") (class "Default")
      (node (ref "C9") (pin "2") (pinfunction "2_2") (pintype "passive"))
      (node (ref "U1") (pin "73") (pinfunction "VCAP_2_73") (pintype "power_in"))
    )
    (net (code "42") (name "Net-(U2-C1+)") (class "Default")
      (node (ref "C11") (pin "2") (pintype "passive"))
      (node (ref "U2") (pin "1") (pinfunction "C1+_1") (pintype "power_in"))
    )
    (net (code "43") (name "Net-(U2-C1-)") (class "Default")
      (node (ref "C11") (pin "1") (pintype "passive"))
      (node (ref "U2") (pin "3") (pinfunction "C1-_3") (pintype "power_in"))
    )
    (net (code "44") (name "Net-(U2-C2+)") (class "Default")
      (node (ref "C19") (pin "2") (pintype "passive"))
      (node (ref "U2") (pin "4") (pinfunction "C2+_4") (pintype "power_in"))
    )
    (net (code "45") (name "Net-(U2-C2-)") (class "Default")
      (node (ref "C19") (pin "1") (pintype "passive"))
      (node (ref "U2") (pin "5") (pinfunction "C2-_5") (pintype "power_in"))
    )
    (net (code "46") (name "Net-(U2-VS+)") (class "Default")
      (node (ref "C14") (pin "1") (pintype "passive"))
      (node (ref "U2") (pin "2") (pinfunction "VS+_2") (pintype "power_in"))
    )
    (net (code "47") (name "Net-(U2-VS-)") (class "Default")
      (node (ref "C20") (pin "2") (pintype "passive"))
      (node (ref "U2") (pin "6") (pinfunction "VS-_6") (pintype "power_in"))
    )
    (net (code "48") (name "Net-(U8-+Vin)") (class "Default")
      (node (ref "C27") (pin "1") (pinfunction "1_1") (pintype "passive"))
      (node (ref "C28") (pin "1") (pinfunction "1_1") (pintype "passive"))
      (node (ref "C29") (pin "1") (pinfunction "1_1") (pintype "passive"))
      (node (ref "F1") (pin "2") (pinfunction "2_2") (pintype "passive"))
      (node (ref "U8") (pin "1") (pinfunction "+Vin_1") (pintype "passive"))
    )
    (net (code "49") (name "Net-(U8-+Vo)") (class "Default")
      (node (ref "F2") (pin "1") (pinfunction "1_1") (pintype "passive"))
      (node (ref "U8") (pin "10") (pinfunction "+Vo_10") (pintype "passive"))
      (node (ref "U8") (pin "9") (pinfunction "Sense+_9") (pintype "passive"))
    )
    (net (code "50") (name "Net-(U8--Vin)") (class "Default")
      (node (ref "C27") (pin "2") (pinfunction "2_2") (pintype "passive"))
      (node (ref "C28") (pin "2") (pinfunction "2_2") (pintype "passive"))
      (node (ref "C29") (pin "2") (pinfunction "2_2") (pintype "passive"))
      (node (ref "J4") (pin "2") (pinfunction "2_2") (pintype "passive"))
      (node (ref "U8") (pin "5") (pinfunction "-Vin_5") (pintype "passive"))
    )
    (net (code "51") (name "OUT+") (class "Default")
      (node (ref "C23") (pin "2") (pinfunction "2_2") (pintype "passive"))
      (node (ref "C26") (pin "1") (pinfunction "1_1") (pintype "passive"))
      (node (ref "J8") (pin "2") (pinfunction "2_2") (pintype "passive"))
      (node (ref "J9") (pin "2") (pinfunction "2_2") (pintype "passive"))
      (node (ref "L1") (pin "1") (pinfunction "1_1") (pintype "passive"))
      (node (ref "R12") (pin "2") (pinfunction "BOT_2") (pintype "passive"))
      (node (ref "R12") (pin "3") (pinfunction "TAP_3") (pintype "passive"))
      (node (ref "R14") (pin "1") (pinfunction "1_1") (pintype "passive"))
    )
    (net (code "52") (name "VCC_5V") (class "Default")
      (node (ref "C36") (pin "1") (pinfunction "1_1") (pintype "passive"))
      (node (ref "LED5") (pin "1") (pinfunction "A_1") (pintype "passive"))
      (node (ref "R11") (pin "1") (pinfunction "1_1") (pintype "passive"))
      (node (ref "R15") (pin "1") (pinfunction "1_1") (pintype "passive"))
      (node (ref "R17") (pin "1") (pinfunction "1_1") (pintype "passive"))
      (node (ref "R6") (pin "1") (pinfunction "1_1") (pintype "passive"))
      (node (ref "R8") (pin "1") (pinfunction "1_1") (pintype "passive"))
      (node (ref "U10") (pin "7") (pinfunction "7_7") (pintype "passive"))
      (node (ref "U10") (pin "8") (pinfunction "8_8") (pintype "passive"))
      (node (ref "U23") (pin "3") (pinfunction "VOUT_3") (pintype "passive"))
      (node (ref "U4") (pin "7") (pinfunction "7_7") (pintype "passive"))
      (node (ref "U4") (pin "8") (pinfunction "8_8") (pintype "passive"))
      (node (ref "U5") (pin "7") (pinfunction "7_7") (pintype "passive"))
      (node (ref "U5") (pin "8") (pinfunction "8_8") (pintype "passive"))
      (node (ref "U7") (pin "7") (pinfunction "7_7") (pintype "passive"))
      (node (ref "U7") (pin "8") (pinfunction "8_8") (pintype "passive"))
      (node (ref "U9") (pin "7") (pinfunction "7_7") (pintype "passive"))
      (node (ref "U9") (pin "8") (pinfunction "8_8") (pintype "passive"))
    )
    (net (code "53") (name "VCC_12V") (class "Default")
      (node (ref "C24") (pin "1") (pinfunction "1_1") (pintype "passive"))
      (node (ref "C25") (pin "2") (pinfunction "2_2") (pintype "passive"))
      (node (ref "C32") (pin "2") (pinfunction "2_2") (pintype "passive"))
      (node (ref "C34") (pin "1") (pinfunction "1_1") (pintype "passive"))
      (node (ref "C35") (pin "1") (pinfunction "1_1") (pintype "passive"))
      (node (ref "J10") (pin "4") (pinfunction "4_4") (pintype "passive"))
      (node (ref "LED4") (pin "1") (pinfunction "A_1") (pintype "passive"))
      (node (ref "U11") (pin "3") (pinfunction "VOUT_3") (pintype "passive"))
      (node (ref "U23") (pin "1") (pinfunction "VIN_1") (pintype "passive"))
      (node (ref "U6") (pin "1") (pinfunction "Vin_1") (pintype "input"))
    )
    (net (code "54") (name "VCC_24V") (class "Default")
      (node (ref "C30") (pin "1") (pinfunction "1_1") (pintype "passive"))
      (node (ref "C31") (pin "2") (pinfunction "2_2") (pintype "passive"))
      (node (ref "C33") (pin "1") (pinfunction "1_1") (pintype "passive"))
      (node (ref "F2") (pin "2") (pinfunction "2_2") (pintype "passive"))
      (node (ref "J5") (pin "3") (pinfunction "3_3") (pintype "passive"))
      (node (ref "J6") (pin "3") (pinfunction "3_3") (pintype "passive"))
      (node (ref "LED3") (pin "1") (pinfunction "A_1") (pintype "passive"))
      (node (ref "TVS1") (pin "2") (pinfunction "K_2") (pintype "passive"))
      (node (ref "U11") (pin "1") (pinfunction "VIN_1") (pintype "passive"))
    )
    (net (code "55") (name "VDD") (class "Default")
      (node (ref "R1") (pin "1") (pinfunction "1_1") (pintype "passive"))
      (node (ref "U1") (pin "21") (pinfunction "VREF+_21") (pintype "power_in"))
      (node (ref "U1") (pin "22") (pinfunction "VDDA_22") (pintype "power_in"))
    )
    (net (code "56") (name "unconnected-(U1A-PA0-WKUP(PA0){slash}USART2_CTS{slash}UART4_TX{slash}ETH_MII_CRS{slash}TIM2_CH1_ETR{slash}TIM5_CH1{slash}TIM8_ETR{slash}EVENTOUT{slash}ADC123_IN0{slash}WKUP-Pad23)") (class "Default")
      (node (ref "U1") (pin "23") (pinfunction "PA0-WKUP(PA0)/USART2_CTS/UART4_TX/ETH_MII_CRS/TIM2_CH1_ETR/TIM5_CH1/TIM8_ETR/EVENTOUT/ADC123_IN0/WKUP_23") (pintype "bidirectional+no_connect"))
    )
    (net (code "57") (name "unconnected-(U1A-PA1{slash}USART2_RTS{slash}UART4_RX{slash}ETH_RMII_REF_CLK{slash}ETH_MII_RX_CLK{slash}TIM5_CH2{slash}TIM2_CH2{slash}EVENTOUT{slash}ADC123_IN1-Pad24)") (class "Default")
      (node (ref "U1") (pin "24") (pinfunction "PA1/USART2_RTS/UART4_RX/ETH_RMII_REF_CLK/ETH_MII_RX_CLK/TIM5_CH2/TIM2_CH2/EVENTOUT/ADC123_IN1_24") (pintype "bidirectional+no_connect"))
    )
    (net (code "58") (name "unconnected-(U1A-PA2{slash}USART2_TX{slash}TIM5_CH3{slash}TIM9_CH1{slash}TIM2_CH3{slash}ETH_MDIO{slash}EVENTOUT{slash}ADC123_IN2-Pad25)") (class "Default")
      (node (ref "U1") (pin "25") (pinfunction "PA2/USART2_TX/TIM5_CH3/TIM9_CH1/TIM2_CH3/ETH_MDIO/EVENTOUT/ADC123_IN2_25") (pintype "bidirectional+no_connect"))
    )
    (net (code "59") (name "unconnected-(U1A-PA3{slash}USART2_RX{slash}TIM5_CH4{slash}TIM9_CH2{slash}TIM2_CH4{slash}OTG_HS_ULPI_D0{slash}ETH_MII_COL{slash}EVENTOUT{slash}ADC123_IN3-Pad26)") (class "Default")
      (node (ref "U1") (pin "26") (pinfunction "PA3/USART2_RX/TIM5_CH4/TIM9_CH2/TIM2_CH4/OTG_HS_ULPI_D0/ETH_MII_COL/EVENTOUT/ADC123_IN3_26") (pintype "bidirectional+no_connect"))
    )
    (net (code "60") (name "unconnected-(U1A-PA4{slash}SPI1_NSS{slash}SPI3_NSS{slash}USART2_CK{slash}DCMI_HSYNC{slash}OTG_HS_SOF{slash}I2S3_WS{slash}EVENTOUT{slash}ADC12_IN4{slash}DAC1_OUT-Pad29)") (class "Default")
      (node (ref "U1") (pin "29") (pinfunction "PA4/SPI1_NSS/SPI3_NSS/USART2_CK/DCMI_HSYNC/OTG_HS_SOF/I2S3_WS/EVENTOUT/ADC12_IN4/DAC1_OUT_29") (pintype "bidirectional"))
    )
    (net (code "61") (name "unconnected-(U1A-PA5{slash}SPI1_SCK{slash}OTG_HS_ULPI_CK{slash}TIM2_CH1_ETR{slash}TIM8_CHIN{slash}EVENTOUT{slash}ADC12_IN5{slash}DAC2_OUT-Pad30)") (class "Default")
      (node (ref "U1") (pin "30") (pinfunction "PA5/SPI1_SCK/OTG_HS_ULPI_CK/TIM2_CH1_ETR/TIM8_CHIN/EVENTOUT/ADC12_IN5/DAC2_OUT_30") (pintype "bidirectional"))
    )
    (net (code "62") (name "unconnected-(U1A-PA6{slash}SPI1_MISO{slash}TIM8_BKIN{slash}TIM13_CH1{slash}DCMI_PIXCLK{slash}TIM3_CH1{slash}TIM1_BKIN{slash}EVENTOUT{slash}ADC12_IN6-Pad31)") (class "Default")
      (node (ref "U1") (pin "31") (pinfunction "PA6/SPI1_MISO/TIM8_BKIN/TIM13_CH1/DCMI_PIXCLK/TIM3_CH1/TIM1_BKIN/EVENTOUT/ADC12_IN6_31") (pintype "bidirectional"))
    )
    (net (code "63") (name "unconnected-(U1A-PA7{slash}SPI1_MOSI{slash}TIM8_CH1N{slash}TIM14_CH1{slash}TIM3_CH2{slash}ETH_MII_RX_DV{slash}TIM1_CH1N{slash}RMII_CRS_DV{slash}EVENTOUT{slash}ADC12_IN7-Pad32)") (class "Default")
      (node (ref "U1") (pin "32") (pinfunction "PA7/SPI1_MOSI/TIM8_CH1N/TIM14_CH1/TIM3_CH2/ETH_MII_RX_DV/TIM1_CH1N/RMII_CRS_DV/EVENTOUT/ADC12_IN7_32") (pintype "bidirectional+no_connect"))
    )
    (net (code "64") (name "unconnected-(U1A-PA8{slash}MCO1{slash}USART1_CK{slash}TIM1_CH1{slash}I2C3_SCL{slash}OTG_FS_SOF{slash}EVENTOUT-Pad67)") (class "Default")
      (node (ref "U1") (pin "67") (pinfunction "PA8/MCO1/USART1_CK/TIM1_CH1/I2C3_SCL/OTG_FS_SOF/EVENTOUT_67") (pintype "bidirectional"))
    )
    (net (code "65") (name "unconnected-(U1A-PA9{slash}USART1_TX{slash}TIM1_CH2{slash}I2C3_SMBA{slash}DCMI_D0{slash}EVENTOUT{slash}OTG_FS_VBUS-Pad68)") (class "Default")
      (node (ref "U1") (pin "68") (pinfunction "PA9/USART1_TX/TIM1_CH2/I2C3_SMBA/DCMI_D0/EVENTOUT/OTG_FS_VBUS_68") (pintype "bidirectional"))
    )
    (net (code "66") (name "unconnected-(U1A-PA10{slash}USART1_RX{slash}TIM1_CH3{slash}OTG_FS_ID{slash}DCMI_D1{slash}EVENTOUT-Pad69)") (class "Default")
      (node (ref "U1") (pin "69") (pinfunction "PA10/USART1_RX/TIM1_CH3/OTG_FS_ID/DCMI_D1/EVENTOUT_69") (pintype "bidirectional"))
    )
    (net (code "67") (name "unconnected-(U1A-PA11{slash}USART1_CTS{slash}CAN1_RX{slash}TIM1_CH4{slash}OTG_FS_DM{slash}EVENTOUT-Pad70)") (class "Default")
      (node (ref "U1") (pin "70") (pinfunction "PA11/USART1_CTS/CAN1_RX/TIM1_CH4/OTG_FS_DM/EVENTOUT_70") (pintype "bidirectional"))
    )
    (net (code "68") (name "unconnected-(U1A-PA12{slash}USART1_RTS{slash}CAN1_TX{slash}TIM1_ETR{slash}OTG_FS_DP{slash}EVENTOUT-Pad71)") (class "Default")
      (node (ref "U1") (pin "71") (pinfunction "PA12/USART1_RTS/CAN1_TX/TIM1_ETR/OTG_FS_DP/EVENTOUT_71") (pintype "bidirectional"))
    )
    (net (code "69") (name "unconnected-(U1A-PB0{slash}TIM3_CH3{slash}TIM8_CH2N{slash}OTG_HS_ULPI_D1{slash}ETH_MII_RXD2{slash}TIM1_CH2N{slash}EVENTOUT{slash}ADC12_IN8-Pad35)") (class "Default")
      (node (ref "U1") (pin "35") (pinfunction "PB0/TIM3_CH3/TIM8_CH2N/OTG_HS_ULPI_D1/ETH_MII_RXD2/TIM1_CH2N/EVENTOUT/ADC12_IN8_35") (pintype "bidirectional"))
    )
    (net (code "70") (name "unconnected-(U1A-PB1{slash}TIM3_CH4{slash}TIM8_CH3N{slash}OTG_HS_ULPI_D2{slash}ETH_MII_RXD3{slash}OTG_HS_INTN{slash}TIM1_CH3N{slash}EVENTOUT{slash}ADC12_IN9-Pad36)") (class "Default")
      (node (ref "U1") (pin "36") (pinfunction "PB1/TIM3_CH4/TIM8_CH3N/OTG_HS_ULPI_D2/ETH_MII_RXD3/OTG_HS_INTN/TIM1_CH3N/EVENTOUT/ADC12_IN9_36") (pintype "bidirectional"))
    )
    (net (code "71") (name "unconnected-(U1A-PB2-BOOT1(PB2){slash}EVENTOUT-Pad37)") (class "Default")
      (node (ref "U1") (pin "37") (pinfunction "PB2-BOOT1(PB2)/EVENTOUT_37") (pintype "bidirectional"))
    )
    (net (code "72") (name "unconnected-(U1A-PB7{slash}I2C1_SDA{slash}FSMC_NL{slash}DCMI_VSYNC{slash}USART1_RX{slash}TIM4_CH2{slash}EVENTOUT-Pad93)") (class "Default")
      (node (ref "U1") (pin "93") (pinfunction "PB7/I2C1_SDA/FSMC_NL/DCMI_VSYNC/USART1_RX/TIM4_CH2/EVENTOUT_93") (pintype "bidirectional"))
    )
    (net (code "73") (name "unconnected-(U1A-PB8{slash}TIM4_CH3{slash}SDIO_D4{slash}TIM10_CH1{slash}DCMI_D6{slash}ETH_MII_TXD3{slash}I2C1_SCL{slash}CAN1_RX{slash}EVENTOUT-Pad95)") (class "Default")
      (node (ref "U1") (pin "95") (pinfunction "PB8/TIM4_CH3/SDIO_D4/TIM10_CH1/DCMI_D6/ETH_MII_TXD3/I2C1_SCL/CAN1_RX/EVENTOUT_95") (pintype "bidirectional+no_connect"))
    )
    (net (code "74") (name "unconnected-(U1A-PB9{slash}SPI2_NSS{slash}I2S2_WS{slash}TIM4_CH4{slash}TIM11_CH1{slash}SDIO_D5{slash}DCMI_D7{slash}I2C1_SDA{slash}CAN1_TX{slash}EVENTOUT-Pad96)") (class "Default")
      (node (ref "U1") (pin "96") (pinfunction "PB9/SPI2_NSS/I2S2_WS/TIM4_CH4/TIM11_CH1/SDIO_D5/DCMI_D7/I2C1_SDA/CAN1_TX/EVENTOUT_96") (pintype "bidirectional+no_connect"))
    )
    (net (code "75") (name "unconnected-(U1A-PB10{slash}SPI2_SCK{slash}I2S2_CK{slash}I2C2_SCL{slash}USART3_TX{slash}OTG_HS_ULPI_D3{slash}ETH_MII_RX_ER{slash}TIM2_CH3{slash}EVENTOUT-Pad47)") (class "Default")
      (node (ref "U1") (pin "47") (pinfunction "PB10/SPI2_SCK/I2S2_CK/I2C2_SCL/USART3_TX/OTG_HS_ULPI_D3/ETH_MII_RX_ER/TIM2_CH3/EVENTOUT_47") (pintype "bidirectional"))
    )
    (net (code "76") (name "unconnected-(U1A-PB11{slash}I2C2_SDA{slash}USART3_RX{slash}OTG_HS_ULPI_D4{slash}ETH_RMII_TX_EN{slash}ETH_MII_TX_EN{slash}TIM2_CH4{slash}EVENTOUT-Pad48)") (class "Default")
      (node (ref "U1") (pin "48") (pinfunction "PB11/I2C2_SDA/USART3_RX/OTG_HS_ULPI_D4/ETH_RMII_TX_EN/ETH_MII_TX_EN/TIM2_CH4/EVENTOUT_48") (pintype "bidirectional"))
    )
    (net (code "77") (name "unconnected-(U1A-PB12{slash}SPI2_NSS{slash}I2S2_WS{slash}I2C2_SMBA{slash}USART3_CK{slash}TIM1_BKIN{slash}CAN2_RX{slash}OTG_HS_ULPI_D5{slash}ETH_RMII_TXD0{slash}ETH_MII_TXD0{slash}OTG_HS_ID{slash}EVENTOUT-Pad51)") (class "Default")
      (node (ref "U1") (pin "51") (pinfunction "PB12/SPI2_NSS/I2S2_WS/I2C2_SMBA/USART3_CK/TIM1_BKIN/CAN2_RX/OTG_HS_ULPI_D5/ETH_RMII_TXD0/ETH_MII_TXD0/OTG_HS_ID/EVENTOUT_51") (pintype "bidirectional"))
    )
    (net (code "78") (name "unconnected-(U1A-PB13{slash}SPI2_SCK{slash}I2S2_CK{slash}USART3_CTS{slash}TIM1_CH1N{slash}CAN2_TX{slash}OTG_HS_ULPI_D6{slash}ETH_RMII_TXD1{slash}ETH_MII_TXD1{slash}EVENTOUT{slash}OTG_HS_VBUS-Pad52)") (class "Default")
      (node (ref "U1") (pin "52") (pinfunction "PB13/SPI2_SCK/I2S2_CK/USART3_CTS/TIM1_CH1N/CAN2_TX/OTG_HS_ULPI_D6/ETH_RMII_TXD1/ETH_MII_TXD1/EVENTOUT/OTG_HS_VBUS_52") (pintype "bidirectional"))
    )
    (net (code "79") (name "unconnected-(U1A-PB14{slash}SPI2_MISO{slash}TIM1_CH2N{slash}TIM12_CH1{slash}OTG_HS_DM{slash}USART3_RTS{slash}TIM8_CH2N{slash}I2S2ext_SD{slash}EVENTOUT-Pad53)") (class "Default")
      (node (ref "U1") (pin "53") (pinfunction "PB14/SPI2_MISO/TIM1_CH2N/TIM12_CH1/OTG_HS_DM/USART3_RTS/TIM8_CH2N/I2S2ext_SD/EVENTOUT_53") (pintype "bidirectional"))
    )
    (net (code "80") (name "unconnected-(U1A-PB15{slash}SPI2_MOSI{slash}I2S2_SD{slash}TIM1_CH3N{slash}TIM8_CH3N{slash}TIM12_CH2{slash}OTG_HS_DP{slash}EVENTOUT-Pad54)") (class "Default")
      (node (ref "U1") (pin "54") (pinfunction "PB15/SPI2_MOSI/I2S2_SD/TIM1_CH3N/TIM8_CH3N/TIM12_CH2/OTG_HS_DP/EVENTOUT_54") (pintype "bidirectional"))
    )
    (net (code "81") (name "unconnected-(U1B-PC0{slash}OTG_HS_ULPI_STP{slash}EVENTOUT{slash}ADC123_IN10-Pad15)") (class "Default")
      (node (ref "U1") (pin "15") (pinfunction "PC0/OTG_HS_ULPI_STP/EVENTOUT/ADC123_IN10_15") (pintype "bidirectional"))
    )
    (net (code "82") (name "unconnected-(U1B-PC1{slash}ETH_MDC{slash}EVENTOUT{slash}ADC123_IN11-Pad16)") (class "Default")
      (node (ref "U1") (pin "16") (pinfunction "PC1/ETH_MDC/EVENTOUT/ADC123_IN11_16") (pintype "bidirectional"))
    )
    (net (code "83") (name "unconnected-(U1B-PC2{slash}SPI2_MISO{slash}OTG_HS_ULPI_DIR{slash}TH_MII_TXD2{slash}I2S2ext_SD{slash}EVENTOUT{slash}ADC123_IN12-Pad17)") (class "Default")
      (node (ref "U1") (pin "17") (pinfunction "PC2/SPI2_MISO/OTG_HS_ULPI_DIR/TH_MII_TXD2/I2S2ext_SD/EVENTOUT/ADC123_IN12_17") (pintype "bidirectional"))
    )
    (net (code "84") (name "unconnected-(U1B-PC3{slash}SPI2_MOSI{slash}I2S2_SD{slash}OTG_HS_ULPI_NXT{slash}ETH_MII_TX_CLK{slash}EVENTOUT{slash}ADC123_IN13-Pad18)") (class "Default")
      (node (ref "U1") (pin "18") (pinfunction "PC3/SPI2_MOSI/I2S2_SD/OTG_HS_ULPI_NXT/ETH_MII_TX_CLK/EVENTOUT/ADC123_IN13_18") (pintype "bidirectional"))
    )
    (net (code "85") (name "unconnected-(U1B-PC4{slash}ETH_RMII_RX_D0{slash}ETH_MII_RX_D0{slash}EVENTOUT{slash}ADC12_IN14-Pad33)") (class "Default")
      (node (ref "U1") (pin "33") (pinfunction "PC4/ETH_RMII_RX_D0/ETH_MII_RX_D0/EVENTOUT/ADC12_IN14_33") (pintype "bidirectional"))
    )
    (net (code "86") (name "unconnected-(U1B-PC5{slash}ETH_RMII_RX_D1{slash}ETH_MII_RX_D1{slash}EVENTOUT{slash}ADC12_IN15-Pad34)") (class "Default")
      (node (ref "U1") (pin "34") (pinfunction "PC5/ETH_RMII_RX_D1/ETH_MII_RX_D1/EVENTOUT/ADC12_IN15_34") (pintype "bidirectional"))
    )
    (net (code "87") (name "unconnected-(U1B-PC6{slash}I2S2_MCK{slash}TIM8_CH1{slash}SDIO_D6{slash}USART6_TX{slash}DCMI_D0{slash}TIM3_CH1{slash}EVENTOUT-Pad63)") (class "Default")
      (node (ref "U1") (pin "63") (pinfunction "PC6/I2S2_MCK/TIM8_CH1/SDIO_D6/USART6_TX/DCMI_D0/TIM3_CH1/EVENTOUT_63") (pintype "bidirectional"))
    )
    (net (code "88") (name "unconnected-(U1B-PC7{slash}I2S3_MCK{slash}TIM8_CH2{slash}SDIO_D7{slash}USART6_RX{slash}DCMI_D1{slash}TIM3_CH2{slash}EVENTOUT-Pad64)") (class "Default")
      (node (ref "U1") (pin "64") (pinfunction "PC7/I2S3_MCK/TIM8_CH2/SDIO_D7/USART6_RX/DCMI_D1/TIM3_CH2/EVENTOUT_64") (pintype "bidirectional"))
    )
    (net (code "89") (name "unconnected-(U1B-PC8{slash}TIM8_CH3{slash}SDIO_D0{slash}TIM3_CH3{slash}USART6_CK{slash}DCMI_D2{slash}EVENTOUT-Pad65)") (class "Default")
      (node (ref "U1") (pin "65") (pinfunction "PC8/TIM8_CH3/SDIO_D0/TIM3_CH3/USART6_CK/DCMI_D2/EVENTOUT_65") (pintype "bidirectional+no_connect"))
    )
    (net (code "90") (name "unconnected-(U1B-PC9{slash}I2S_CKIN{slash}MCO2{slash}TIM8_CH4{slash}SDIO_D1{slash}{slash}I2C3_SDA{slash}DCMI_D3{slash}TIM3_CH4{slash}EVENTOUT-Pad66)") (class "Default")
      (node (ref "U1") (pin "66") (pinfunction "PC9/I2S_CKIN/MCO2/TIM8_CH4/SDIO_D1//I2C3_SDA/DCMI_D3/TIM3_CH4/EVENTOUT_66") (pintype "bidirectional"))
    )
    (net (code "91") (name "unconnected-(U1B-PC10{slash}SPI3_SCK{slash}I2S3_CK{slash}UART4_TX{slash}SDIO_D2{slash}DCMI_D8{slash}USART3_TX{slash}EVENTOUT-Pad78)") (class "Default")
      (node (ref "U1") (pin "78") (pinfunction "PC10/SPI3_SCK/I2S3_CK/UART4_TX/SDIO_D2/DCMI_D8/USART3_TX/EVENTOUT_78") (pintype "bidirectional"))
    )
    (net (code "92") (name "unconnected-(U1B-PC11{slash}UART4_RX{slash}SPI3_MISO{slash}SDIO_D3{slash}DCMI_D4{slash}USART3_RX{slash}I2S3ext_SD{slash}EVENTOUT-Pad79)") (class "Default")
      (node (ref "U1") (pin "79") (pinfunction "PC11/UART4_RX/SPI3_MISO/SDIO_D3/DCMI_D4/USART3_RX/I2S3ext_SD/EVENTOUT_79") (pintype "bidirectional"))
    )
    (net (code "93") (name "unconnected-(U1B-PC12{slash}UART5_TX{slash}SDIO_CK{slash}DCMI_D9{slash}SPI3_MOSI{slash}I2S3_SD{slash}USART3_CK{slash}EVENTOUT-Pad80)") (class "Default")
      (node (ref "U1") (pin "80") (pinfunction "PC12/UART5_TX/SDIO_CK/DCMI_D9/SPI3_MOSI/I2S3_SD/USART3_CK/EVENTOUT_80") (pintype "bidirectional"))
    )
    (net (code "94") (name "unconnected-(U1B-PC13{slash}EVENTOUT{slash}RTC_AF1-Pad7)") (class "Default")
      (node (ref "U1") (pin "7") (pinfunction "PC13/EVENTOUT/RTC_AF1_7") (pintype "bidirectional"))
    )
    (net (code "95") (name "unconnected-(U1B-PD0{slash}FSMC_D2{slash}CAN1_RX{slash}EVENTOUT-Pad81)") (class "Default")
      (node (ref "U1") (pin "81") (pinfunction "PD0/FSMC_D2/CAN1_RX/EVENTOUT_81") (pintype "bidirectional"))
    )
    (net (code "96") (name "unconnected-(U1B-PD1{slash}FSMC_D3{slash}CAN1_TX{slash}EVENTOUT-Pad82)") (class "Default")
      (node (ref "U1") (pin "82") (pinfunction "PD1/FSMC_D3/CAN1_TX/EVENTOUT_82") (pintype "bidirectional"))
    )
    (net (code "97") (name "unconnected-(U1B-PD2{slash}TIM3_ETR{slash}UART5_RX{slash}SDIO_CMD{slash}DCMI_D11{slash}EVENTOUT-Pad83)") (class "Default")
      (node (ref "U1") (pin "83") (pinfunction "PD2/TIM3_ETR/UART5_RX/SDIO_CMD/DCMI_D11/EVENTOUT_83") (pintype "bidirectional"))
    )
    (net (code "98") (name "unconnected-(U1B-PD3{slash}FSMC_CLK{slash}USART2_CTS{slash}EVENTOUT-Pad84)") (class "Default")
      (node (ref "U1") (pin "84") (pinfunction "PD3/FSMC_CLK/USART2_CTS/EVENTOUT_84") (pintype "bidirectional"))
    )
    (net (code "99") (name "unconnected-(U1B-PD4{slash}FSMC_NOE{slash}USART2_RTS{slash}EVENTOUT-Pad85)") (class "Default")
      (node (ref "U1") (pin "85") (pinfunction "PD4/FSMC_NOE/USART2_RTS/EVENTOUT_85") (pintype "bidirectional"))
    )
    (net (code "100") (name "unconnected-(U1B-PD5{slash}FSMC_NWE{slash}USART2_TX{slash}EVENTOUT-Pad86)") (class "Default")
      (node (ref "U1") (pin "86") (pinfunction "PD5/FSMC_NWE/USART2_TX/EVENTOUT_86") (pintype "bidirectional"))
    )
    (net (code "101") (name "unconnected-(U1B-PD6{slash}FSMC_NWAIT{slash}USART2_RX{slash}EVENTOUT-Pad87)") (class "Default")
      (node (ref "U1") (pin "87") (pinfunction "PD6/FSMC_NWAIT/USART2_RX/EVENTOUT_87") (pintype "bidirectional"))
    )
    (net (code "102") (name "unconnected-(U1B-PD7{slash}USART2_CK{slash}FSMC_NE1{slash}FSMC_NCE2{slash}EVENTOUT-Pad88)") (class "Default")
      (node (ref "U1") (pin "88") (pinfunction "PD7/USART2_CK/FSMC_NE1/FSMC_NCE2/EVENTOUT_88") (pintype "bidirectional"))
    )
    (net (code "103") (name "unconnected-(U1B-PD10{slash}FSMC_D15{slash}USART3_CK{slash}EVENTOUT-Pad57)") (class "Default")
      (node (ref "U1") (pin "57") (pinfunction "PD10/FSMC_D15/USART3_CK/EVENTOUT_57") (pintype "bidirectional"))
    )
    (net (code "104") (name "unconnected-(U1B-PD11{slash}FSMC_CLE{slash}FSMC_A16{slash}USART3_CTS{slash}EVENTOUT-Pad58)") (class "Default")
      (node (ref "U1") (pin "58") (pinfunction "PD11/FSMC_CLE/FSMC_A16/USART3_CTS/EVENTOUT_58") (pintype "bidirectional"))
    )
    (net (code "105") (name "unconnected-(U1B-PD12{slash}FSMC_ALE{slash}FSMC_A17{slash}TIM4_CH1{slash}USART3_RTS{slash}EVENTOUT-Pad59)") (class "Default")
      (node (ref "U1") (pin "59") (pinfunction "PD12/FSMC_ALE/FSMC_A17/TIM4_CH1/USART3_RTS/EVENTOUT_59") (pintype "bidirectional"))
    )
    (net (code "106") (name "unconnected-(U1B-PD13{slash}FSMC_A18{slash}TIM4_CH2{slash}EVENTOUT-Pad60)") (class "Default")
      (node (ref "U1") (pin "60") (pinfunction "PD13/FSMC_A18/TIM4_CH2/EVENTOUT_60") (pintype "bidirectional"))
    )
    (net (code "107") (name "unconnected-(U1B-PD14{slash}FSMC_D0{slash}TIM4_CH3{slash}EVENTOUT{slash}EVENTOUT-Pad61)") (class "Default")
      (node (ref "U1") (pin "61") (pinfunction "PD14/FSMC_D0/TIM4_CH3/EVENTOUT/EVENTOUT_61") (pintype "bidirectional+no_connect"))
    )
    (net (code "108") (name "unconnected-(U1B-PD15{slash}FSMC_D1{slash}TIM4_CH4{slash}EVENTOUT-Pad62)") (class "Default")
      (node (ref "U1") (pin "62") (pinfunction "PD15/FSMC_D1/TIM4_CH4/EVENTOUT_62") (pintype "bidirectional+no_connect"))
    )
    (net (code "109") (name "unconnected-(U1C-PE0{slash}TIM4_ETR{slash}FSMC_NBL0{slash}DCMI_D2{slash}EVENTOUT-Pad97)") (class "Default")
      (node (ref "U1") (pin "97") (pinfunction "PE0/TIM4_ETR/FSMC_NBL0/DCMI_D2/EVENTOUT_97") (pintype "bidirectional"))
    )
    (net (code "110") (name "unconnected-(U1C-PE1{slash}FSMC_NBL1{slash}DCMI_D3{slash}EVENTOUT-Pad98)") (class "Default")
      (node (ref "U1") (pin "98") (pinfunction "PE1/FSMC_NBL1/DCMI_D3/EVENTOUT_98") (pintype "bidirectional"))
    )
    (net (code "111") (name "unconnected-(U1C-PE2{slash}TRACECLK{slash}FSMC_A23{slash}ETH_MII_TXD3{slash}EVENTOUT-Pad1)") (class "Default")
      (node (ref "U1") (pin "1") (pinfunction "PE2/TRACECLK/FSMC_A23/ETH_MII_TXD3/EVENTOUT_1") (pintype "bidirectional"))
    )
    (net (code "112") (name "unconnected-(U1C-PE3{slash}TRACED0{slash}FSMC_A19{slash}EVENTOUT-Pad2)") (class "Default")
      (node (ref "U1") (pin "2") (pinfunction "PE3/TRACED0/FSMC_A19/EVENTOUT_2") (pintype "bidirectional"))
    )
    (net (code "113") (name "unconnected-(U1C-PE4{slash}TRACED1{slash}FSMC_A20{slash}DCMI_D4{slash}EVENTOUT-Pad3)") (class "Default")
      (node (ref "U1") (pin "3") (pinfunction "PE4/TRACED1/FSMC_A20/DCMI_D4/EVENTOUT_3") (pintype "bidirectional"))
    )
    (net (code "114") (name "unconnected-(U1C-PE5{slash}TRACED2{slash}FSMC_A21{slash}TIM9_CH1{slash}DCMI_D6{slash}EVENTOUT-Pad4)") (class "Default")
      (node (ref "U1") (pin "4") (pinfunction "PE5/TRACED2/FSMC_A21/TIM9_CH1/DCMI_D6/EVENTOUT_4") (pintype "bidirectional"))
    )
    (net (code "115") (name "unconnected-(U1C-PE6{slash}TRACED3{slash}FSMC_A22{slash}TIM9_CH2{slash}DCMI_D7{slash}EVENTOUT-Pad5)") (class "Default")
      (node (ref "U1") (pin "5") (pinfunction "PE6/TRACED3/FSMC_A22/TIM9_CH2/DCMI_D7/EVENTOUT_5") (pintype "bidirectional"))
    )
    (net (code "116") (name "unconnected-(U1C-PE7{slash}FSMC_D4{slash}TIM1_ETR{slash}EVENTOUT-Pad38)") (class "Default")
      (node (ref "U1") (pin "38") (pinfunction "PE7/FSMC_D4/TIM1_ETR/EVENTOUT_38") (pintype "bidirectional"))
    )
    (net (code "117") (name "unconnected-(U1C-PE8{slash}FSMC_D5{slash}TIM1_CH1N{slash}EVENTOUT-Pad39)") (class "Default")
      (node (ref "U1") (pin "39") (pinfunction "PE8/FSMC_D5/TIM1_CH1N/EVENTOUT_39") (pintype "bidirectional"))
    )
    (net (code "118") (name "unconnected-(U1C-PE9{slash}FSMC_D6{slash}TIM1_CH1{slash}EVENTOUT-Pad40)") (class "Default")
      (node (ref "U1") (pin "40") (pinfunction "PE9/FSMC_D6/TIM1_CH1/EVENTOUT_40") (pintype "bidirectional"))
    )
    (net (code "119") (name "unconnected-(U1C-PE10{slash}FSMC_D7{slash}TIM1_CH2N{slash}EVENTOUT-Pad41)") (class "Default")
      (node (ref "U1") (pin "41") (pinfunction "PE10/FSMC_D7/TIM1_CH2N/EVENTOUT_41") (pintype "bidirectional"))
    )
    (net (code "120") (name "unconnected-(U1C-PE11{slash}FSMC_D8{slash}TIM1_CH2{slash}EVENTOUT-Pad42)") (class "Default")
      (node (ref "U1") (pin "42") (pinfunction "PE11/FSMC_D8/TIM1_CH2/EVENTOUT_42") (pintype "bidirectional"))
    )
    (net (code "121") (name "unconnected-(U1C-PE12{slash}FSMC_D9{slash}TIM1_CH3N{slash}EVENTOUT-Pad43)") (class "Default")
      (node (ref "U1") (pin "43") (pinfunction "PE12/FSMC_D9/TIM1_CH3N/EVENTOUT_43") (pintype "bidirectional"))
    )
    (net (code "122") (name "unconnected-(U1C-PE13{slash}FSMC_D10{slash}TIM1_CH3{slash}EVENTOUT-Pad44)") (class "Default")
      (node (ref "U1") (pin "44") (pinfunction "PE13/FSMC_D10/TIM1_CH3/EVENTOUT_44") (pintype "bidirectional+no_connect"))
    )
    (net (code "123") (name "unconnected-(U1C-PE14{slash}FSMC_D11{slash}TIM1_CH4{slash}EVENTOUT-Pad45)") (class "Default")
      (node (ref "U1") (pin "45") (pinfunction "PE14/FSMC_D11/TIM1_CH4/EVENTOUT_45") (pintype "bidirectional+no_connect"))
    )
    (net (code "124") (name "unconnected-(U1C-PE15{slash}FSMC_D12{slash}TIM1_BKIN{slash}EVENTOUT-Pad46)") (class "Default")
      (node (ref "U1") (pin "46") (pinfunction "PE15/FSMC_D12/TIM1_BKIN/EVENTOUT_46") (pintype "bidirectional"))
    )
    (net (code "125") (name "unconnected-(U2-R2IN-Pad8)") (class "Default")
      (node (ref "U2") (pin "8") (pinfunction "R2IN_8") (pintype "power_in"))
    )
    (net (code "126") (name "unconnected-(U2-R2OUT-Pad9)") (class "Default")
      (node (ref "U2") (pin "9") (pinfunction "R2OUT_9") (pintype "power_in"))
    )
    (net (code "127") (name "unconnected-(U2-T2IN-Pad10)") (class "Default")
      (node (ref "U2") (pin "10") (pinfunction "T2IN_10") (pintype "power_in"))
    )
    (net (code "128") (name "unconnected-(U2-T2OUT-Pad7)") (class "Default")
      (node (ref "U2") (pin "7") (pinfunction "T2OUT_7") (pintype "power_in"))
    )
    (net (code "129") (name "unconnected-(U4-Pad1)") (class "Default")
      (node (ref "U4") (pin "1") (pinfunction "1_1") (pintype "passive"))
    )
    (net (code "130") (name "unconnected-(U4-Pad4)") (class "Default")
      (node (ref "U4") (pin "4") (pinfunction "4_4") (pintype "passive"))
    )
    (net (code "131") (name "unconnected-(U5-Pad1)") (class "Default")
      (node (ref "U5") (pin "1") (pinfunction "1_1") (pintype "passive"))
    )
    (net (code "132") (name "unconnected-(U5-Pad4)") (class "Default")
      (node (ref "U5") (pin "4") (pinfunction "4_4") (pintype "passive"))
    )
    (net (code "133") (name "unconnected-(U7-Pad1)") (class "Default")
      (node (ref "U7") (pin "1") (pinfunction "1_1") (pintype "passive"))
    )
    (net (code "134") (name "unconnected-(U7-Pad4)") (class "Default")
      (node (ref "U7") (pin "4") (pinfunction "4_4") (pintype "passive"))
    )
    (net (code "135") (name "unconnected-(U8-Ctrl-Pad3)") (class "Default")
      (node (ref "U8") (pin "3") (pinfunction "Ctrl_3") (pintype "passive"))
    )
    (net (code "136") (name "unconnected-(U8-N{slash}C-Pad2)") (class "Default")
      (node (ref "U8") (pin "2") (pinfunction "N/C_2") (pintype "passive+no_connect"))
    )
    (net (code "137") (name "unconnected-(U8-N{slash}C-Pad4)") (class "Default")
      (node (ref "U8") (pin "4") (pinfunction "N/C_4") (pintype "passive+no_connect"))
    )
    (net (code "138") (name "unconnected-(U8-Trim-Pad8)") (class "Default")
      (node (ref "U8") (pin "8") (pinfunction "Trim_8") (pintype "passive"))
    )
    (net (code "139") (name "unconnected-(U9-Pad1)") (class "Default")
      (node (ref "U9") (pin "1") (pinfunction "1_1") (pintype "passive"))
    )
    (net (code "140") (name "unconnected-(U9-Pad4)") (class "Default")
      (node (ref "U9") (pin "4") (pinfunction "4_4") (pintype "passive"))
    )
    (net (code "141") (name "unconnected-(U10-Pad1)") (class "Default")
      (node (ref "U10") (pin "1") (pinfunction "1_1") (pintype "passive"))
    )
    (net (code "142") (name "unconnected-(U10-Pad4)") (class "Default")
      (node (ref "U10") (pin "4") (pinfunction "4_4") (pintype "passive"))
    )
  )
)
